# MCU.net
KiCad netlist of a schematic drawn in Altium Designer
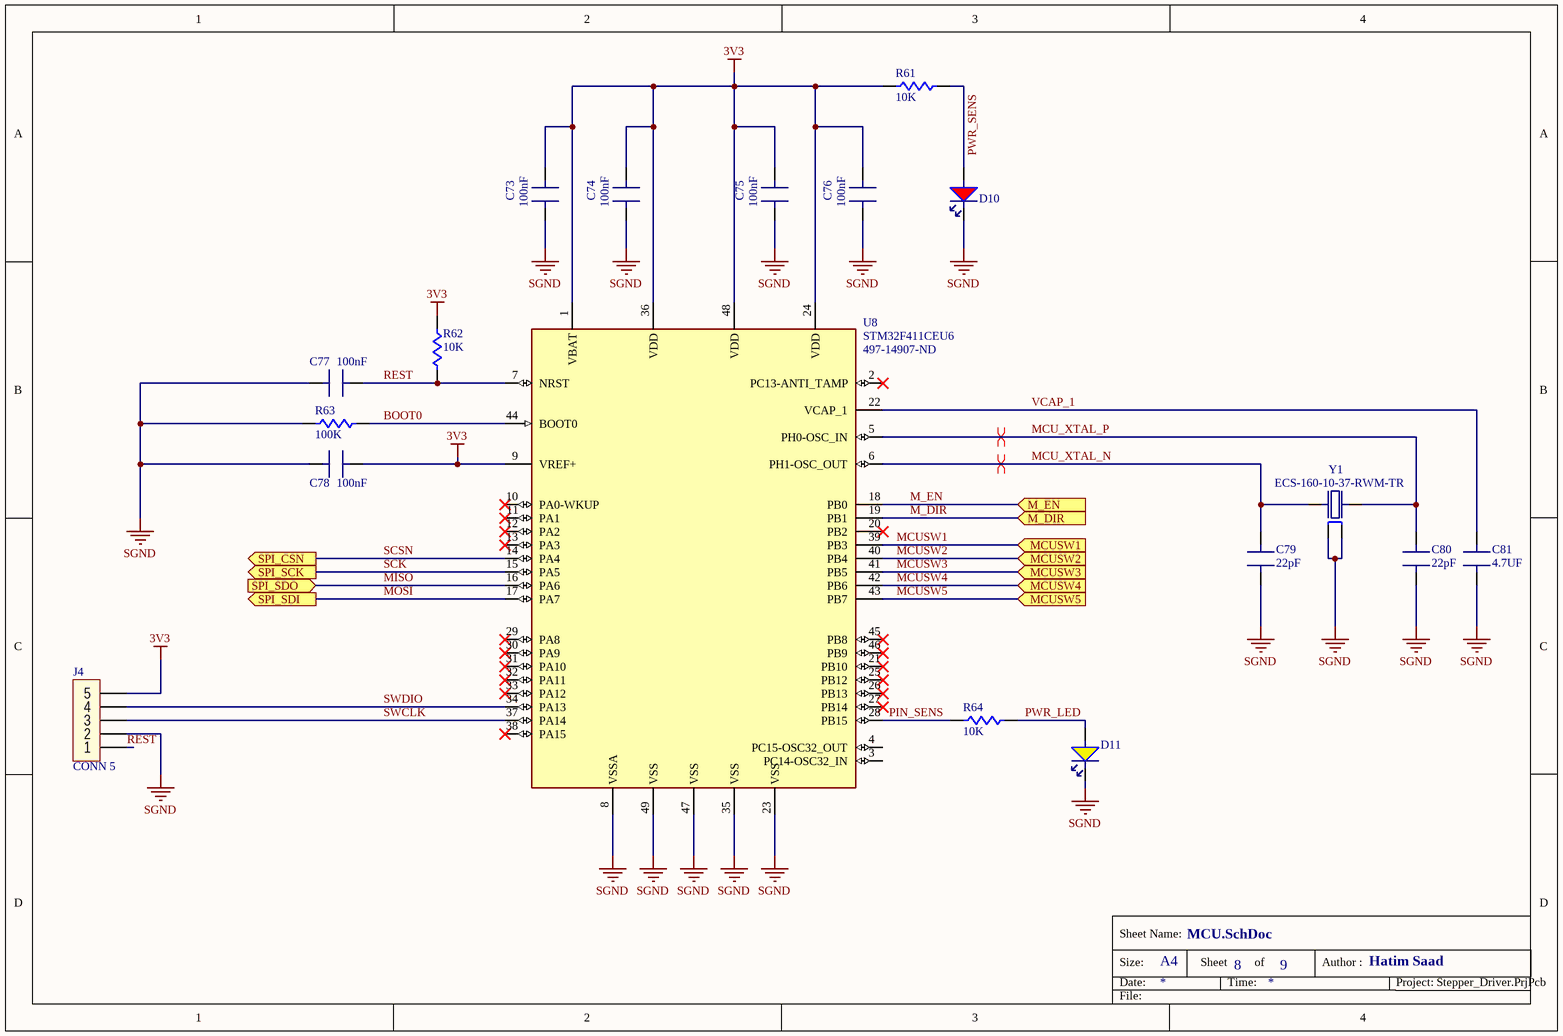
[diagram p0: MCU.SchDoc]

(export (version "E")
  (design (tool "Eeschema 10.0.6"))
  (components
    (comp (ref "C73")
      (value "100nF")
      (footprint "CAP: 0603")
      (description "CAP SMD 0603")
      (libsource (lib "HZSchLib") (part "CAP 0603"))
    )
    (comp (ref "C74")
      (value "100nF")
      (footprint "CAP: 0603")
      (description "CAP SMD 0603")
      (libsource (lib "HZSchLib") (part "CAP 0603"))
    )
    (comp (ref "C75")
      (value "100nF")
      (footprint "CAP: 0603")
      (description "CAP SMD 0603")
      (libsource (lib "HZSchLib") (part "CAP 0603"))
    )
    (comp (ref "C76")
      (value "100nF")
      (footprint "CAP: 0603")
      (description "CAP SMD 0603")
      (libsource (lib "HZSchLib") (part "CAP 0603"))
    )
    (comp (ref "C77")
      (value "100nF")
      (footprint "CAP: 0603")
      (description "CAP SMD 0603")
      (libsource (lib "HZSchLib") (part "CAP 0603"))
    )
    (comp (ref "C78")
      (value "100nF")
      (footprint "CAP: 0603")
      (description "CAP SMD 0603")
      (libsource (lib "HZSchLib") (part "CAP 0603"))
    )
    (comp (ref "C79")
      (value "22pF")
      (footprint "CAP: 0603")
      (description "CAP SMD 0603")
      (libsource (lib "HZSchLib") (part "CAP 0603"))
    )
    (comp (ref "C80")
      (value "22pF")
      (footprint "CAP: 0603")
      (description "CAP SMD 0603")
      (libsource (lib "HZSchLib") (part "CAP 0603"))
    )
    (comp (ref "C81")
      (value "4.7UF")
      (footprint "CAP: 0603")
      (description "CAP SMD 0603")
      (libsource (lib "HZSchLib") (part "CAP 0603"))
    )
    (comp (ref "D10")
      (value "RED")
      (footprint "LED: 0603R")
      (description "LED RED CLEAR 0603 SMD")
      (libsource (lib "HZSchLib") (part "LED RED 0603"))
    )
    (comp (ref "D11")
      (value "YELLOW")
      (footprint "LED: 0603Y")
      (description "LED YELLOW CLEAR 0603 SMD")
      (libsource (lib "HZSchLib") (part "LED YELLOW 0603"))
    )
    (comp (ref "J4")
      (value "CONN 5")
      (footprint "CON: PLS-5")
      (libsource (lib "BEEC44SchLib") (part "CONN 5"))
    )
    (comp (ref "R61")
      (value "10K")
      (footprint "RES: 0603")
      (description "RES SMD 0603")
      (libsource (lib "HZSchLib") (part "RES 0603"))
    )
    (comp (ref "R62")
      (value "10K")
      (footprint "RES: 0603")
      (description "RES SMD 0603")
      (libsource (lib "HZSchLib") (part "RES 0603"))
    )
    (comp (ref "R63")
      (value "100K")
      (footprint "RES: 0603")
      (description "RES SMD 0603")
      (libsource (lib "HZSchLib") (part "RES 0603"))
    )
    (comp (ref "R64")
      (value "10K")
      (footprint "RES: 0603")
      (description "RES SMD 0603")
      (libsource (lib "HZSchLib") (part "RES 0603"))
    )
    (comp (ref "U8")
      (value "STM32F411CEU6")
      (footprint "STM32F411CEU6")
      (description "IC MCU 32BIT 512KB FLSH 48UFQFPN")
      (fields
        (field (name "MANUFACTURER") "STMicroelectronics")
        (field (name "SUPPLIER PART NUMBER 1") "497-14907-ND")
      )
      (libsource (lib "BEEC44SchLib") (part "STM32F411CEU6"))
    )
    (comp (ref "Y1")
      (value "ECS-160-10-37-RWM-TR")
      (footprint "OSC: 2016")
      (description "CRYSTAL 16.0000MHZ 10PF SMD")
      (libsource (lib "HZSchLib") (part "XC2119DKR-ND"))
    )
  )
  (nets
    (net (code "1") (name "/BOOT0") (class "Default")
      (node (ref "R63") (pin "2") (pinfunction "2_2") (pintype "passive"))
      (node (ref "U8") (pin "44") (pinfunction "BOOT0_44") (pintype "input"))
    )
    (net (code "2") (name "/MCUSW1") (class "Default")
      (node (ref "U8") (pin "39") (pinfunction "PB3_39") (pintype "passive"))
    )
    (net (code "3") (name "/MCUSW2") (class "Default")
      (node (ref "U8") (pin "40") (pinfunction "PB4_40") (pintype "passive"))
    )
    (net (code "4") (name "/MCUSW3") (class "Default")
      (node (ref "U8") (pin "41") (pinfunction "PB5_41") (pintype "passive"))
    )
    (net (code "5") (name "/MCUSW4") (class "Default")
      (node (ref "U8") (pin "42") (pinfunction "PB6_42") (pintype "passive"))
    )
    (net (code "6") (name "/MCUSW5") (class "Default")
      (node (ref "U8") (pin "43") (pinfunction "PB7_43") (pintype "passive"))
    )
    (net (code "7") (name "/MCU_XTAL_N") (class "Default")
      (node (ref "C79") (pin "1") (pinfunction "A_1") (pintype "passive"))
      (node (ref "U8") (pin "6") (pinfunction "PH1-OSC_OUT_6") (pintype "bidirectional"))
      (node (ref "Y1") (pin "3") (pinfunction "XTAL2_3") (pintype "passive"))
    )
    (net (code "8") (name "/MCU_XTAL_P") (class "Default")
      (node (ref "C80") (pin "1") (pinfunction "A_1") (pintype "passive"))
      (node (ref "U8") (pin "5") (pinfunction "PH0-OSC_IN_5") (pintype "bidirectional"))
      (node (ref "Y1") (pin "1") (pinfunction "XTAL1_1") (pintype "passive"))
    )
    (net (code "9") (name "/MISO") (class "Default")
      (node (ref "U8") (pin "16") (pinfunction "PA6_16") (pintype "bidirectional"))
    )
    (net (code "10") (name "/MOSI") (class "Default")
      (node (ref "U8") (pin "17") (pinfunction "PA7_17") (pintype "bidirectional"))
    )
    (net (code "11") (name "/M_DIR") (class "Default")
      (node (ref "U8") (pin "19") (pinfunction "PB1_19") (pintype "passive"))
    )
    (net (code "12") (name "/M_EN") (class "Default")
      (node (ref "U8") (pin "18") (pinfunction "PB0_18") (pintype "passive"))
    )
    (net (code "13") (name "/PIN_SENS") (class "Default")
      (node (ref "R64") (pin "2") (pinfunction "2_2") (pintype "passive"))
      (node (ref "U8") (pin "28") (pinfunction "PB15_28") (pintype "bidirectional"))
    )
    (net (code "14") (name "/PWR_LED") (class "Default")
      (node (ref "D11") (pin "2") (pinfunction "A_2") (pintype "passive"))
      (node (ref "R64") (pin "1") (pinfunction "1_1") (pintype "passive"))
    )
    (net (code "15") (name "/PWR_SENS") (class "Default")
      (node (ref "D10") (pin "2") (pinfunction "A_2") (pintype "passive"))
      (node (ref "R61") (pin "2") (pinfunction "2_2") (pintype "passive"))
    )
    (net (code "16") (name "/REST") (class "Default")
      (node (ref "C77") (pin "1") (pinfunction "A_1") (pintype "passive"))
      (node (ref "J4") (pin "1") (pinfunction "1_1") (pintype "passive"))
      (node (ref "R62") (pin "2") (pinfunction "2_2") (pintype "passive"))
      (node (ref "U8") (pin "7") (pinfunction "NRST_7") (pintype "bidirectional"))
    )
    (net (code "17") (name "/SCK") (class "Default")
      (node (ref "U8") (pin "15") (pinfunction "PA5_15") (pintype "bidirectional"))
    )
    (net (code "18") (name "/SCSN") (class "Default")
      (node (ref "U8") (pin "14") (pinfunction "PA4_14") (pintype "bidirectional"))
    )
    (net (code "19") (name "/SWCLK") (class "Default")
      (node (ref "J4") (pin "3") (pinfunction "3_3") (pintype "power_in"))
      (node (ref "U8") (pin "37") (pinfunction "PA14_37") (pintype "bidirectional"))
    )
    (net (code "20") (name "/SWDIO") (class "Default")
      (node (ref "J4") (pin "4") (pinfunction "4_4") (pintype "power_in"))
      (node (ref "U8") (pin "34") (pinfunction "PA13_34") (pintype "bidirectional"))
    )
    (net (code "21") (name "/VCAP_1") (class "Default")
      (node (ref "C81") (pin "1") (pinfunction "A_1") (pintype "passive"))
      (node (ref "U8") (pin "22") (pinfunction "VCAP_1_22") (pintype "power_in"))
    )
    (net (code "22") (name "3V3") (class "Default")
      (node (ref "C73") (pin "2") (pinfunction "B_2") (pintype "passive"))
      (node (ref "C74") (pin "2") (pinfunction "B_2") (pintype "passive"))
      (node (ref "C75") (pin "2") (pinfunction "B_2") (pintype "passive"))
      (node (ref "C76") (pin "2") (pinfunction "B_2") (pintype "passive"))
      (node (ref "C78") (pin "1") (pinfunction "A_1") (pintype "passive"))
      (node (ref "J4") (pin "5") (pinfunction "5_5") (pintype "power_in"))
      (node (ref "R61") (pin "1") (pinfunction "1_1") (pintype "passive"))
      (node (ref "R62") (pin "1") (pinfunction "1_1") (pintype "passive"))
      (node (ref "U8") (pin "1") (pinfunction "VBAT_1") (pintype "power_in"))
      (node (ref "U8") (pin "24") (pinfunction "VDD_24") (pintype "power_in"))
      (node (ref "U8") (pin "36") (pinfunction "VDD_36") (pintype "power_in"))
      (node (ref "U8") (pin "48") (pinfunction "VDD_48") (pintype "power_in"))
      (node (ref "U8") (pin "9") (pinfunction "VREF+_9") (pintype "power_in"))
    )
    (net (code "23") (name "SGND") (class "Default")
      (node (ref "C73") (pin "1") (pinfunction "A_1") (pintype "passive"))
      (node (ref "C74") (pin "1") (pinfunction "A_1") (pintype "passive"))
      (node (ref "C75") (pin "1") (pinfunction "A_1") (pintype "passive"))
      (node (ref "C76") (pin "1") (pinfunction "A_1") (pintype "passive"))
      (node (ref "C77") (pin "2") (pinfunction "B_2") (pintype "passive"))
      (node (ref "C78") (pin "2") (pinfunction "B_2") (pintype "passive"))
      (node (ref "C79") (pin "2") (pinfunction "B_2") (pintype "passive"))
      (node (ref "C80") (pin "2") (pinfunction "B_2") (pintype "passive"))
      (node (ref "C81") (pin "2") (pinfunction "B_2") (pintype "passive"))
      (node (ref "D10") (pin "1") (pinfunction "C_1") (pintype "passive"))
      (node (ref "D11") (pin "1") (pinfunction "C_1") (pintype "passive"))
      (node (ref "J4") (pin "2") (pinfunction "2_2") (pintype "passive"))
      (node (ref "R63") (pin "1") (pinfunction "1_1") (pintype "passive"))
      (node (ref "U8") (pin "23") (pinfunction "VSS_23") (pintype "power_in"))
      (node (ref "U8") (pin "35") (pinfunction "VSS_35") (pintype "power_in"))
      (node (ref "U8") (pin "47") (pinfunction "VSS_47") (pintype "power_in"))
      (node (ref "U8") (pin "49") (pinfunction "VSS_49") (pintype "power_in"))
      (node (ref "U8") (pin "8") (pinfunction "VSSA_8") (pintype "power_in"))
      (node (ref "Y1") (pin "2") (pinfunction "GND_2") (pintype "passive"))
      (node (ref "Y1") (pin "4") (pinfunction "GND_4") (pintype "passive"))
    )
    (net (code "24") (name "unconnected-(U8-PA0-WKUP-Pad10)") (class "Default")
      (node (ref "U8") (pin "10") (pinfunction "PA0-WKUP_10") (pintype "bidirectional+no_connect"))
    )
    (net (code "25") (name "unconnected-(U8-PA1-Pad11)") (class "Default")
      (node (ref "U8") (pin "11") (pinfunction "PA1_11") (pintype "bidirectional+no_connect"))
    )
    (net (code "26") (name "unconnected-(U8-PA2-Pad12)") (class "Default")
      (node (ref "U8") (pin "12") (pinfunction "PA2_12") (pintype "bidirectional+no_connect"))
    )
    (net (code "27") (name "unconnected-(U8-PA3-Pad13)") (class "Default")
      (node (ref "U8") (pin "13") (pinfunction "PA3_13") (pintype "bidirectional+no_connect"))
    )
    (net (code "28") (name "unconnected-(U8-PA8-Pad29)") (class "Default")
      (node (ref "U8") (pin "29") (pinfunction "PA8_29") (pintype "bidirectional+no_connect"))
    )
    (net (code "29") (name "unconnected-(U8-PA9-Pad30)") (class "Default")
      (node (ref "U8") (pin "30") (pinfunction "PA9_30") (pintype "bidirectional+no_connect"))
    )
    (net (code "30") (name "unconnected-(U8-PA10-Pad31)") (class "Default")
      (node (ref "U8") (pin "31") (pinfunction "PA10_31") (pintype "bidirectional+no_connect"))
    )
    (net (code "31") (name "unconnected-(U8-PA11-Pad32)") (class "Default")
      (node (ref "U8") (pin "32") (pinfunction "PA11_32") (pintype "bidirectional+no_connect"))
    )
    (net (code "32") (name "unconnected-(U8-PA12-Pad33)") (class "Default")
      (node (ref "U8") (pin "33") (pinfunction "PA12_33") (pintype "bidirectional+no_connect"))
    )
    (net (code "33") (name "unconnected-(U8-PA15-Pad38)") (class "Default")
      (node (ref "U8") (pin "38") (pinfunction "PA15_38") (pintype "bidirectional+no_connect"))
    )
    (net (code "34") (name "unconnected-(U8-PB2-Pad20)") (class "Default")
      (node (ref "U8") (pin "20") (pinfunction "PB2_20") (pintype "passive+no_connect"))
    )
    (net (code "35") (name "unconnected-(U8-PB8-Pad45)") (class "Default")
      (node (ref "U8") (pin "45") (pinfunction "PB8_45") (pintype "bidirectional+no_connect"))
    )
    (net (code "36") (name "unconnected-(U8-PB9-Pad46)") (class "Default")
      (node (ref "U8") (pin "46") (pinfunction "PB9_46") (pintype "bidirectional+no_connect"))
    )
    (net (code "37") (name "unconnected-(U8-PB10-Pad21)") (class "Default")
      (node (ref "U8") (pin "21") (pinfunction "PB10_21") (pintype "bidirectional+no_connect"))
    )
    (net (code "38") (name "unconnected-(U8-PB12-Pad25)") (class "Default")
      (node (ref "U8") (pin "25") (pinfunction "PB12_25") (pintype "bidirectional+no_connect"))
    )
    (net (code "39") (name "unconnected-(U8-PB13-Pad26)") (class "Default")
      (node (ref "U8") (pin "26") (pinfunction "PB13_26") (pintype "bidirectional+no_connect"))
    )
    (net (code "40") (name "unconnected-(U8-PB14-Pad27)") (class "Default")
      (node (ref "U8") (pin "27") (pinfunction "PB14_27") (pintype "bidirectional+no_connect"))
    )
    (net (code "41") (name "unconnected-(U8-PC13-ANTI_TAMP-Pad2)") (class "Default")
      (node (ref "U8") (pin "2") (pinfunction "PC13-ANTI_TAMP_2") (pintype "bidirectional+no_connect"))
    )
    (net (code "42") (name "unconnected-(U8-PC14-OSC32_IN-Pad3)") (class "Default")
      (node (ref "U8") (pin "3") (pinfunction "PC14-OSC32_IN_3") (pintype "bidirectional"))
    )
    (net (code "43") (name "unconnected-(U8-PC15-OSC32_OUT-Pad4)") (class "Default")
      (node (ref "U8") (pin "4") (pinfunction "PC15-OSC32_OUT_4") (pintype "bidirectional"))
    )
  )
)
